# SCH_Konwerter-Hal-Elektrody_2026-02-06.net
KiCad netlist of a schematic drawn in EasyEDA
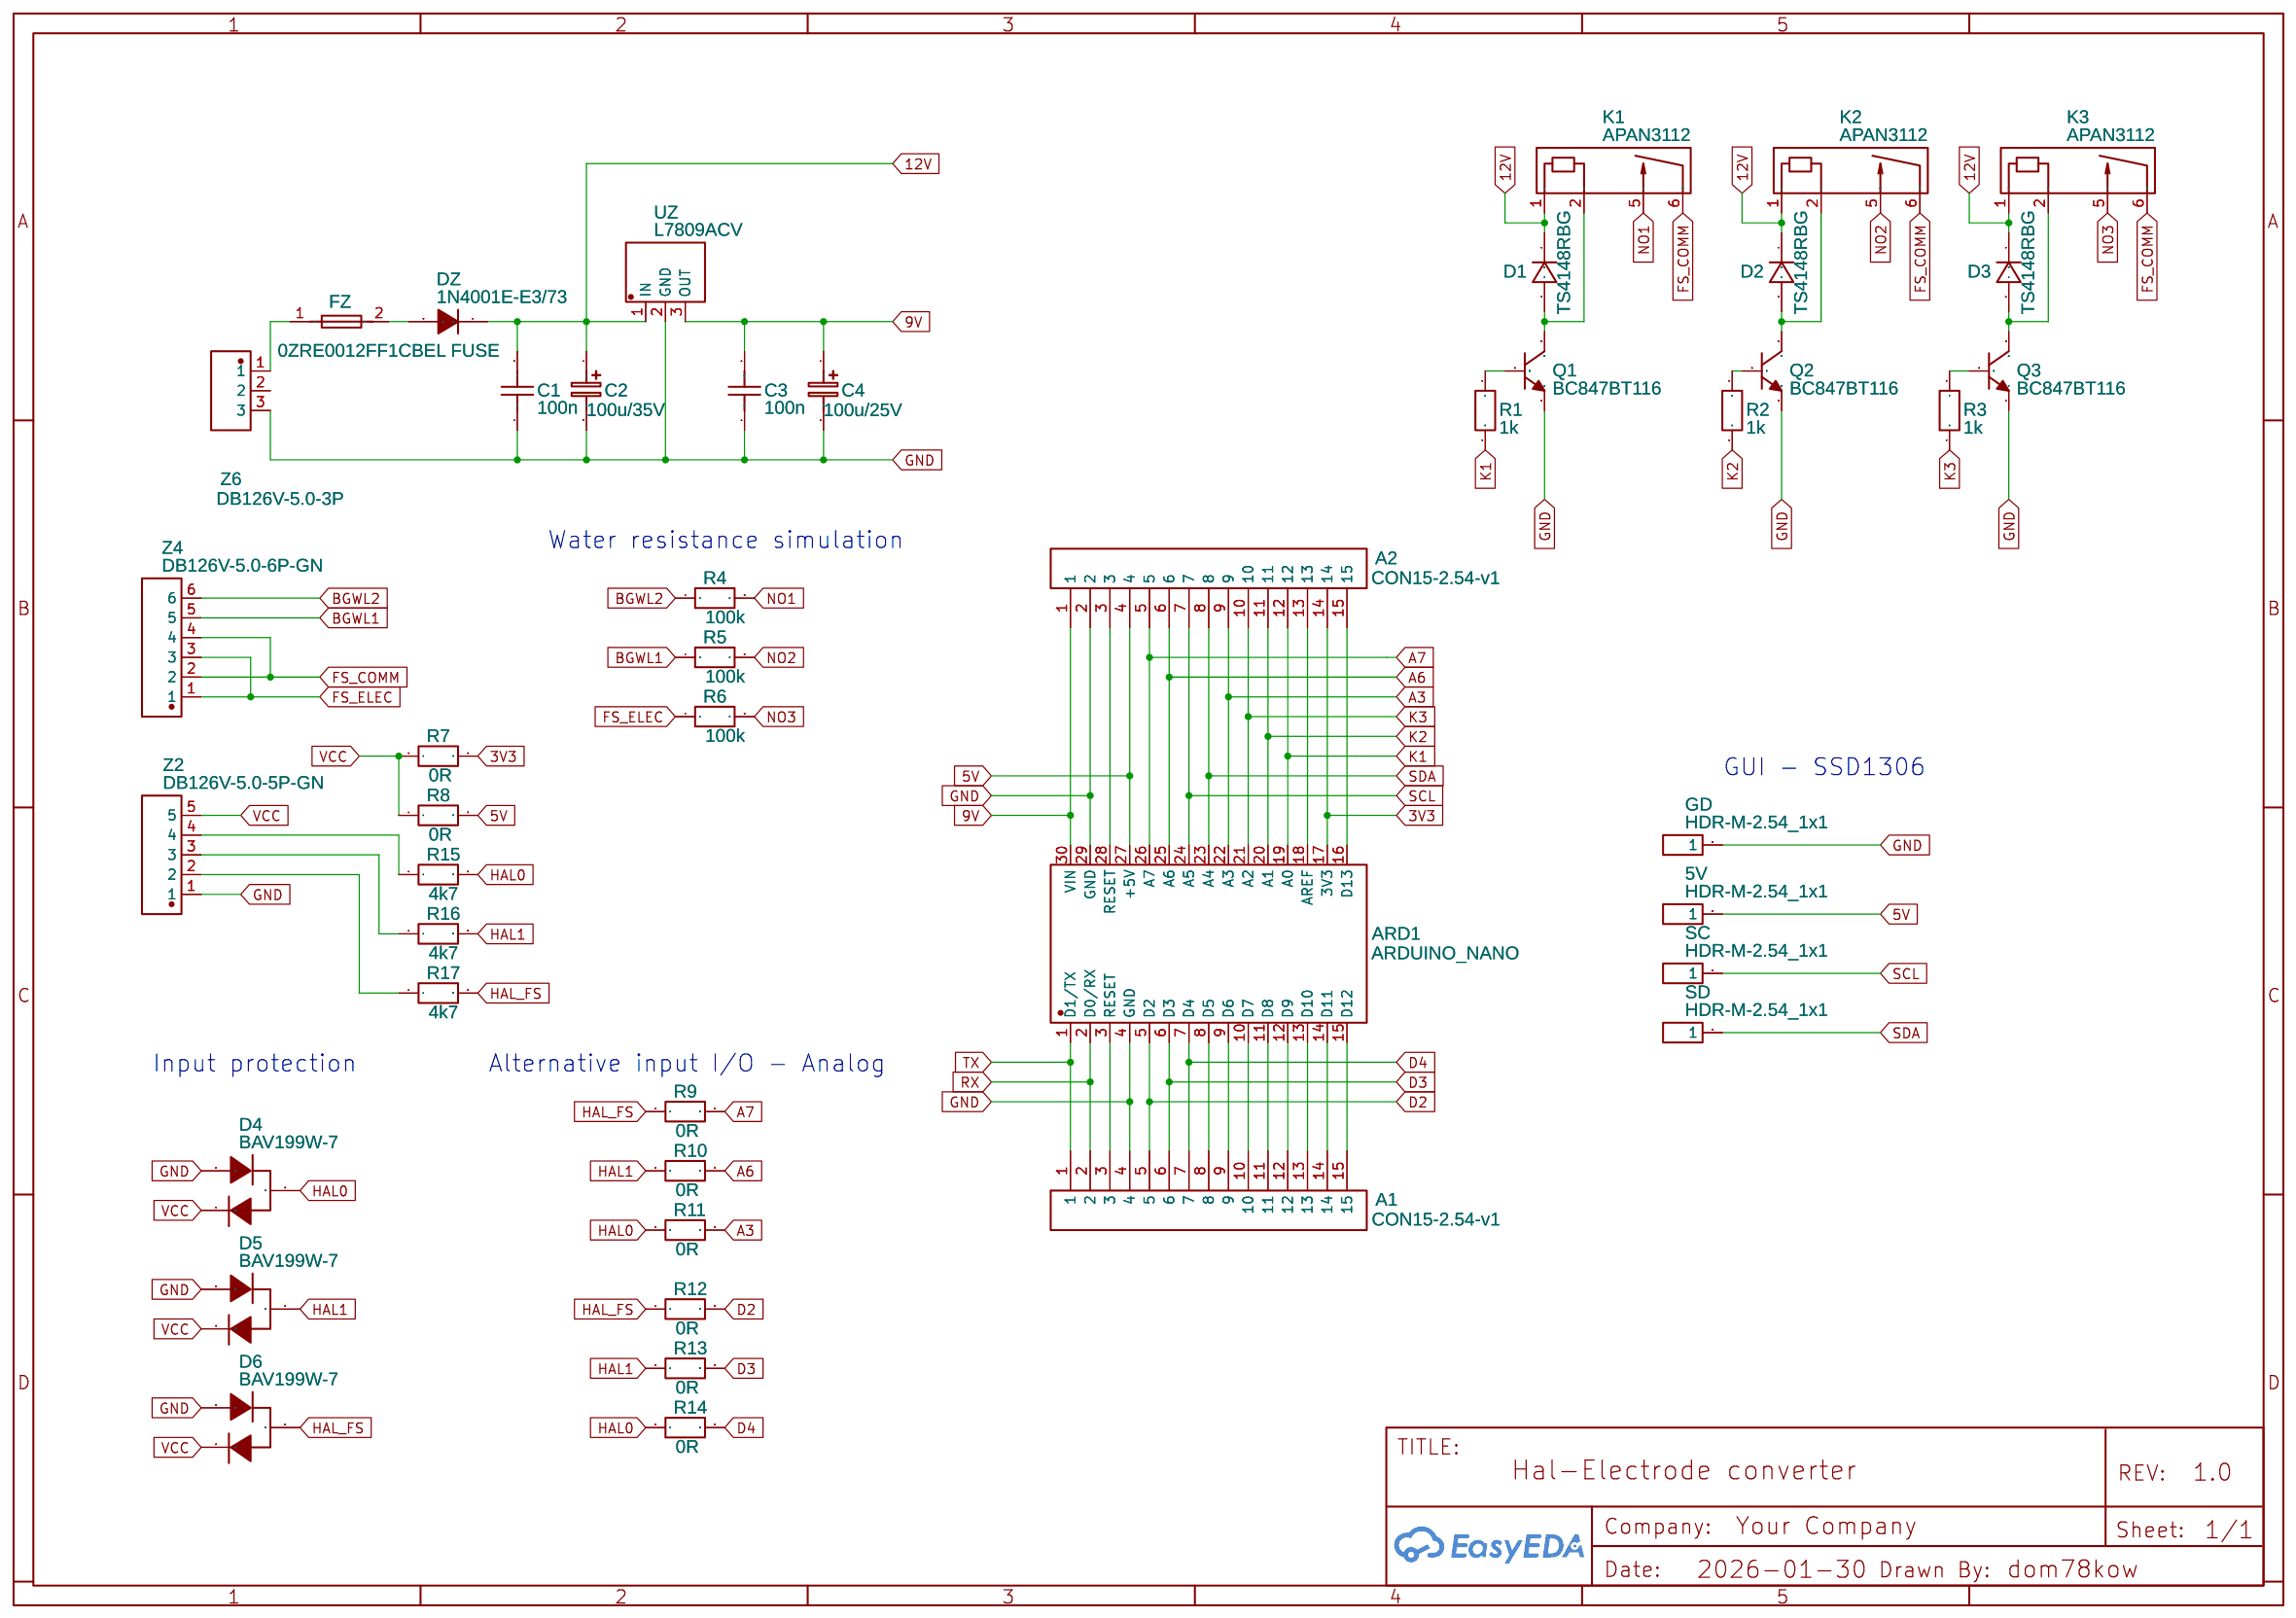
[diagram p0: schematic sheet]

(export (version "E")
  (design (tool "Eeschema 10.0.6"))
  (components
    (comp (ref "5V") (value "HDR-M-2.54_1x1") (libsource (lib "") (part "HDR-M-2.54_1x1_1")))
    (comp (ref "A1") (value "CON15-2.54-v1") (libsource (lib "") (part "CON15-2.54-v1")))
    (comp (ref "A2") (value "CON15-2.54-v1") (libsource (lib "") (part "CON15-2.54-v1_1")))
    (comp (ref "ARD1") (value "ARDUINO_NANO") (libsource (lib "") (part "ARDUINO_NANO")))
    (comp (ref "C1") (value "100n") (libsource (lib "") (part "C_1206_US")))
    (comp (ref "C2") (value "100u/35V") (libsource (lib "") (part "CE_TH_D5.0×F2.0_EU")))
    (comp (ref "C3") (value "100n") (libsource (lib "") (part "C_1206_US")))
    (comp (ref "C4") (value "100u/25V") (libsource (lib "") (part "CE_TH_D5.0×F2.0_EU")))
    (comp (ref "D1")
      (value "TS4148RBG")
      (fields (field (name "Manufacturer Part") "CD4148WP") (field (name "Manufacturer") "SUP(美隆)"))
      (libsource (lib "") (part "CD4148WP_C112371"))
    )
    (comp (ref "D2")
      (value "TS4148RBG")
      (fields (field (name "Manufacturer Part") "CD4148WP") (field (name "Manufacturer") "SUP(美隆)"))
      (libsource (lib "") (part "CD4148WP_C112371"))
    )
    (comp (ref "D3")
      (value "TS4148RBG")
      (fields (field (name "Manufacturer Part") "CD4148WP") (field (name "Manufacturer") "SUP(美隆)"))
      (libsource (lib "") (part "CD4148WP_C112371"))
    )
    (comp (ref "D4")
      (value "BAV199W-7")
      (fields (field (name "Manufacturer") "DIODES(美台)"))
      (libsource (lib "") (part "BAV199W-7"))
    )
    (comp (ref "D5")
      (value "BAV199W-7")
      (fields (field (name "Manufacturer") "DIODES(美台)"))
      (libsource (lib "") (part "BAV199W-7"))
    )
    (comp (ref "D6")
      (value "BAV199W-7")
      (fields (field (name "Manufacturer") "DIODES(美台)"))
      (libsource (lib "") (part "BAV199W-7"))
    )
    (comp (ref "DZ")
      (value "1N4001E-E3/73")
      (fields (field (name "Manufacturer") "VISHAY(威世)"))
      (libsource (lib "") (part "1N4001E-E3/73"))
    )
    (comp (ref "FZ")
      (value "0ZRE0012FF1CBEL FUSE")
      (fields (field (name "Manufacturer Part") "SCT 2.5A") (field (name "Manufacturer") "Skygate(天宇匹克)"))
      (libsource (lib "") (part "SCT 2.5A"))
    )
    (comp (ref "GD") (value "HDR-M-2.54_1x1") (libsource (lib "") (part "HDR-M-2.54_1x1_2")))
    (comp (ref "K1")
      (value "APAN3112")
      (fields (field (name "Manufacturer Part") "APAN3105") (field (name "Manufacturer") "PANASONIC(松下)"))
      (libsource (lib "") (part "APAN3105"))
    )
    (comp (ref "K2")
      (value "APAN3112")
      (fields (field (name "Manufacturer Part") "APAN3105") (field (name "Manufacturer") "PANASONIC(松下)"))
      (libsource (lib "") (part "APAN3105"))
    )
    (comp (ref "K3")
      (value "APAN3112")
      (fields (field (name "Manufacturer Part") "APAN3105") (field (name "Manufacturer") "PANASONIC(松下)"))
      (libsource (lib "") (part "APAN3105"))
    )
    (comp (ref "Q1")
      (value "BC847BT116")
      (fields (field (name "Manufacturer") "ROHM(罗姆)"))
      (libsource (lib "") (part "BC847BT116"))
    )
    (comp (ref "Q2")
      (value "BC847BT116")
      (fields (field (name "Manufacturer") "ROHM(罗姆)"))
      (libsource (lib "") (part "BC847BT116"))
    )
    (comp (ref "Q3")
      (value "BC847BT116")
      (fields (field (name "Manufacturer") "ROHM(罗姆)"))
      (libsource (lib "") (part "BC847BT116"))
    )
    (comp (ref "R1") (value "1k") (libsource (lib "") (part "R_1206_EU_1")))
    (comp (ref "R2") (value "1k") (libsource (lib "") (part "R_1206_EU_1")))
    (comp (ref "R3") (value "1k") (libsource (lib "") (part "R_1206_EU_1")))
    (comp (ref "R4") (value "100k") (libsource (lib "") (part "R_1206_EU")))
    (comp (ref "R5") (value "100k") (libsource (lib "") (part "R_1206_EU")))
    (comp (ref "R6") (value "100k") (libsource (lib "") (part "R_1206_EU")))
    (comp (ref "R7") (value "0R") (libsource (lib "") (part "R_1206_EU")))
    (comp (ref "R8") (value "0R") (libsource (lib "") (part "R_1206_EU")))
    (comp (ref "R9") (value "0R") (libsource (lib "") (part "R_1206_EU")))
    (comp (ref "R10") (value "0R") (libsource (lib "") (part "R_1206_EU")))
    (comp (ref "R11") (value "0R") (libsource (lib "") (part "R_1206_EU")))
    (comp (ref "R12") (value "0R") (libsource (lib "") (part "R_1206_EU")))
    (comp (ref "R13") (value "0R") (libsource (lib "") (part "R_1206_EU")))
    (comp (ref "R14") (value "0R") (libsource (lib "") (part "R_1206_EU")))
    (comp (ref "R15") (value "4k7") (libsource (lib "") (part "R_1206_EU")))
    (comp (ref "R16") (value "4k7") (libsource (lib "") (part "R_1206_EU")))
    (comp (ref "R17") (value "4k7") (libsource (lib "") (part "R_1206_EU")))
    (comp (ref "SC") (value "HDR-M-2.54_1x1") (libsource (lib "") (part "HDR-M-2.54_1x1")))
    (comp (ref "SD") (value "HDR-M-2.54_1x1") (libsource (lib "") (part "HDR-M-2.54_1x1_3")))
    (comp (ref "UZ")
      (value "L7809ACV")
      (fields (field (name "Manufacturer Part") "L7812ACV") (field (name "Manufacturer") "ST(意法半导体)"))
      (libsource (lib "") (part "L7812ACV"))
    )
    (comp (ref "Z2")
      (value "DB126V-5.0-5P-GN")
      (fields
        (field (name "Manufacturer Part") "DB126V-5.0-5P-GN-P")
        (field (name "Manufacturer") "DIBO(地博电气)")
      )
      (libsource (lib "") (part "DB126V-5.0-5P-GN"))
    )
    (comp (ref "Z4")
      (value "DB126V-5.0-6P-GN")
      (fields
        (field (name "Manufacturer Part") "DB126V-5.0-6P-GN-P")
        (field (name "Manufacturer") "DORABO(地博电气)")
      )
      (libsource (lib "") (part "DB126V-5.0-6P-GN"))
    )
    (comp (ref "Z6")
      (value "DB126V-5.0-3P")
      (fields
        (field (name "Manufacturer Part") "DB126V-5.0-3P-GN")
        (field (name "Manufacturer") "DORABO(地博电气)")
      )
      (libsource (lib "") (part "DB126V-5.0-3P"))
    )
  )
  (nets
    (net (code "1") (name "3V3") (class "Default")
      (node (ref "A2") (pin "14") (pinfunction "14_14") (pintype "unspecified"))
      (node (ref "ARD1") (pin "17") (pinfunction "3V3_17") (pintype "unspecified"))
      (node (ref "R7") (pin "2") (pinfunction "2_2") (pintype "unspecified"))
    )
    (net (code "2") (name "5V") (class "Default")
      (node (ref "5V") (pin "1") (pinfunction "1_1") (pintype "input"))
      (node (ref "A2") (pin "4") (pinfunction "4_4") (pintype "unspecified"))
      (node (ref "ARD1") (pin "27") (pinfunction "+5V_27") (pintype "unspecified"))
      (node (ref "R8") (pin "2") (pinfunction "2_2") (pintype "unspecified"))
    )
    (net (code "3") (name "9V") (class "Default")
      (node (ref "A2") (pin "1") (pinfunction "1_1") (pintype "unspecified"))
      (node (ref "ARD1") (pin "30") (pinfunction "VIN_30") (pintype "unspecified"))
      (node (ref "C3") (pin "2") (pinfunction "2_2") (pintype "unspecified"))
      (node (ref "C4") (pin "1") (pinfunction "1_1") (pintype "unspecified"))
      (node (ref "UZ") (pin "3") (pinfunction "OUT_3") (pintype "unspecified"))
    )
    (net (code "4") (name "12V") (class "Default")
      (node (ref "C1") (pin "2") (pinfunction "2_2") (pintype "unspecified"))
      (node (ref "C2") (pin "1") (pinfunction "1_1") (pintype "unspecified"))
      (node (ref "D1") (pin "1") (pinfunction "C_1") (pintype "unspecified"))
      (node (ref "D2") (pin "1") (pinfunction "C_1") (pintype "unspecified"))
      (node (ref "D3") (pin "1") (pinfunction "C_1") (pintype "unspecified"))
      (node (ref "DZ") (pin "1") (pinfunction "K_1") (pintype "unspecified"))
      (node (ref "K1") (pin "1") (pinfunction "1_1") (pintype "unspecified"))
      (node (ref "K2") (pin "1") (pinfunction "1_1") (pintype "unspecified"))
      (node (ref "K3") (pin "1") (pinfunction "1_1") (pintype "unspecified"))
      (node (ref "UZ") (pin "1") (pinfunction "IN_1") (pintype "unspecified"))
    )
    (net (code "5") (name "A3") (class "Default")
      (node (ref "A2") (pin "9") (pinfunction "9_9") (pintype "unspecified"))
      (node (ref "ARD1") (pin "22") (pinfunction "A3_22") (pintype "unspecified"))
      (node (ref "R11") (pin "2") (pinfunction "2_2") (pintype "unspecified"))
    )
    (net (code "6") (name "A6") (class "Default")
      (node (ref "A2") (pin "6") (pinfunction "6_6") (pintype "unspecified"))
      (node (ref "ARD1") (pin "25") (pinfunction "A6_25") (pintype "unspecified"))
      (node (ref "R10") (pin "2") (pinfunction "2_2") (pintype "unspecified"))
    )
    (net (code "7") (name "A7") (class "Default")
      (node (ref "A2") (pin "5") (pinfunction "5_5") (pintype "unspecified"))
      (node (ref "ARD1") (pin "26") (pinfunction "A7_26") (pintype "unspecified"))
      (node (ref "R9") (pin "2") (pinfunction "2_2") (pintype "unspecified"))
    )
    (net (code "8") (name "BGWL1") (class "Default")
      (node (ref "R5") (pin "1") (pinfunction "1_1") (pintype "unspecified"))
      (node (ref "Z4") (pin "5") (pinfunction "5_5") (pintype "unspecified"))
    )
    (net (code "9") (name "BGWL2") (class "Default")
      (node (ref "R4") (pin "1") (pinfunction "1_1") (pintype "unspecified"))
      (node (ref "Z4") (pin "6") (pinfunction "6_6") (pintype "unspecified"))
    )
    (net (code "10") (name "D2") (class "Default")
      (node (ref "A1") (pin "5") (pinfunction "5_5") (pintype "unspecified"))
      (node (ref "ARD1") (pin "5") (pinfunction "D2_5") (pintype "unspecified"))
      (node (ref "R12") (pin "2") (pinfunction "2_2") (pintype "unspecified"))
    )
    (net (code "11") (name "D3") (class "Default")
      (node (ref "A1") (pin "6") (pinfunction "6_6") (pintype "unspecified"))
      (node (ref "ARD1") (pin "6") (pinfunction "D3_6") (pintype "unspecified"))
      (node (ref "R13") (pin "2") (pinfunction "2_2") (pintype "unspecified"))
    )
    (net (code "12") (name "D4") (class "Default")
      (node (ref "A1") (pin "7") (pinfunction "7_7") (pintype "unspecified"))
      (node (ref "ARD1") (pin "7") (pinfunction "D4_7") (pintype "unspecified"))
      (node (ref "R14") (pin "2") (pinfunction "2_2") (pintype "unspecified"))
    )
    (net (code "13") (name "FS_COMM") (class "Default")
      (node (ref "K1") (pin "6") (pinfunction "COM_6") (pintype "unspecified"))
      (node (ref "K2") (pin "6") (pinfunction "COM_6") (pintype "unspecified"))
      (node (ref "K3") (pin "6") (pinfunction "COM_6") (pintype "unspecified"))
      (node (ref "Z4") (pin "2") (pinfunction "2_2") (pintype "unspecified"))
      (node (ref "Z4") (pin "4") (pinfunction "4_4") (pintype "unspecified"))
    )
    (net (code "14") (name "FS_ELEC") (class "Default")
      (node (ref "R6") (pin "1") (pinfunction "1_1") (pintype "unspecified"))
      (node (ref "Z4") (pin "1") (pinfunction "1_1") (pintype "unspecified"))
      (node (ref "Z4") (pin "3") (pinfunction "3_3") (pintype "unspecified"))
    )
    (net (code "15") (name "GND") (class "Default")
      (node (ref "A1") (pin "4") (pinfunction "4_4") (pintype "unspecified"))
      (node (ref "A2") (pin "2") (pinfunction "2_2") (pintype "unspecified"))
      (node (ref "ARD1") (pin "29") (pinfunction "GND_29") (pintype "unspecified"))
      (node (ref "ARD1") (pin "4") (pinfunction "GND_4") (pintype "unspecified"))
      (node (ref "C1") (pin "1") (pinfunction "1_1") (pintype "unspecified"))
      (node (ref "C2") (pin "2") (pinfunction "2_2") (pintype "unspecified"))
      (node (ref "C3") (pin "1") (pinfunction "1_1") (pintype "unspecified"))
      (node (ref "C4") (pin "2") (pinfunction "2_2") (pintype "unspecified"))
      (node (ref "D4") (pin "1") (pinfunction "1_1") (pintype "unspecified"))
      (node (ref "D5") (pin "1") (pinfunction "1_1") (pintype "unspecified"))
      (node (ref "D6") (pin "1") (pinfunction "1_1") (pintype "unspecified"))
      (node (ref "GD") (pin "1") (pinfunction "1_1") (pintype "input"))
      (node (ref "Q1") (pin "1") (pinfunction "E_1") (pintype "input"))
      (node (ref "Q2") (pin "1") (pinfunction "E_1") (pintype "input"))
      (node (ref "Q3") (pin "1") (pinfunction "E_1") (pintype "input"))
      (node (ref "UZ") (pin "2") (pinfunction "GND_2") (pintype "unspecified"))
      (node (ref "Z2") (pin "1") (pinfunction "1_1") (pintype "unspecified"))
      (node (ref "Z6") (pin "3") (pinfunction "3_3") (pintype "unspecified"))
    )
    (net (code "16") (name "HAL0") (class "Default")
      (node (ref "D4") (pin "3") (pinfunction "3_3") (pintype "unspecified"))
      (node (ref "R11") (pin "1") (pinfunction "1_1") (pintype "unspecified"))
      (node (ref "R14") (pin "1") (pinfunction "1_1") (pintype "unspecified"))
      (node (ref "R15") (pin "2") (pinfunction "2_2") (pintype "unspecified"))
    )
    (net (code "17") (name "HAL1") (class "Default")
      (node (ref "D5") (pin "3") (pinfunction "3_3") (pintype "unspecified"))
      (node (ref "R10") (pin "1") (pinfunction "1_1") (pintype "unspecified"))
      (node (ref "R13") (pin "1") (pinfunction "1_1") (pintype "unspecified"))
      (node (ref "R16") (pin "2") (pinfunction "2_2") (pintype "unspecified"))
    )
    (net (code "18") (name "HAL_FS") (class "Default")
      (node (ref "D6") (pin "3") (pinfunction "3_3") (pintype "unspecified"))
      (node (ref "R12") (pin "1") (pinfunction "1_1") (pintype "unspecified"))
      (node (ref "R17") (pin "2") (pinfunction "2_2") (pintype "unspecified"))
      (node (ref "R9") (pin "1") (pinfunction "1_1") (pintype "unspecified"))
    )
    (net (code "19") (name "K1") (class "Default")
      (node (ref "A2") (pin "12") (pinfunction "12_12") (pintype "unspecified"))
      (node (ref "ARD1") (pin "19") (pinfunction "A0_19") (pintype "unspecified"))
      (node (ref "R1") (pin "2") (pinfunction "2_2") (pintype "unspecified"))
    )
    (net (code "20") (name "K2") (class "Default")
      (node (ref "A2") (pin "11") (pinfunction "11_11") (pintype "unspecified"))
      (node (ref "ARD1") (pin "20") (pinfunction "A1_20") (pintype "unspecified"))
      (node (ref "R2") (pin "2") (pinfunction "2_2") (pintype "unspecified"))
    )
    (net (code "21") (name "K3") (class "Default")
      (node (ref "A2") (pin "10") (pinfunction "10_10") (pintype "unspecified"))
      (node (ref "ARD1") (pin "21") (pinfunction "A2_21") (pintype "unspecified"))
      (node (ref "R3") (pin "2") (pinfunction "2_2") (pintype "unspecified"))
    )
    (net (code "22") (name "NO1") (class "Default")
      (node (ref "K1") (pin "5") (pinfunction "ON_5") (pintype "unspecified"))
      (node (ref "R4") (pin "2") (pinfunction "2_2") (pintype "unspecified"))
    )
    (net (code "23") (name "NO2") (class "Default")
      (node (ref "K2") (pin "5") (pinfunction "ON_5") (pintype "unspecified"))
      (node (ref "R5") (pin "2") (pinfunction "2_2") (pintype "unspecified"))
    )
    (net (code "24") (name "NO3") (class "Default")
      (node (ref "K3") (pin "5") (pinfunction "ON_5") (pintype "unspecified"))
      (node (ref "R6") (pin "2") (pinfunction "2_2") (pintype "unspecified"))
    )
    (net (code "25") (name "Net-(A1-Pad3)") (class "Default")
      (node (ref "A1") (pin "3") (pinfunction "3_3") (pintype "unspecified"))
      (node (ref "ARD1") (pin "3") (pinfunction "RESET_3") (pintype "unspecified"))
    )
    (net (code "26") (name "Net-(A2-Pad3)") (class "Default")
      (node (ref "A2") (pin "3") (pinfunction "3_3") (pintype "unspecified"))
      (node (ref "ARD1") (pin "28") (pinfunction "RESET_28") (pintype "unspecified"))
    )
    (net (code "27") (name "Net-(ARD1-AREF)") (class "Default")
      (node (ref "A2") (pin "13") (pinfunction "13_13") (pintype "unspecified"))
      (node (ref "ARD1") (pin "18") (pinfunction "AREF_18") (pintype "unspecified"))
    )
    (net (code "28") (name "Net-(ARD1-D5)") (class "Default")
      (node (ref "A1") (pin "8") (pinfunction "8_8") (pintype "unspecified"))
      (node (ref "ARD1") (pin "8") (pinfunction "D5_8") (pintype "unspecified"))
    )
    (net (code "29") (name "Net-(ARD1-D6)") (class "Default")
      (node (ref "A1") (pin "9") (pinfunction "9_9") (pintype "unspecified"))
      (node (ref "ARD1") (pin "9") (pinfunction "D6_9") (pintype "unspecified"))
    )
    (net (code "30") (name "Net-(ARD1-D7)") (class "Default")
      (node (ref "A1") (pin "10") (pinfunction "10_10") (pintype "unspecified"))
      (node (ref "ARD1") (pin "10") (pinfunction "D7_10") (pintype "unspecified"))
    )
    (net (code "31") (name "Net-(ARD1-D8)") (class "Default")
      (node (ref "A1") (pin "11") (pinfunction "11_11") (pintype "unspecified"))
      (node (ref "ARD1") (pin "11") (pinfunction "D8_11") (pintype "unspecified"))
    )
    (net (code "32") (name "Net-(ARD1-D9)") (class "Default")
      (node (ref "A1") (pin "12") (pinfunction "12_12") (pintype "unspecified"))
      (node (ref "ARD1") (pin "12") (pinfunction "D9_12") (pintype "unspecified"))
    )
    (net (code "33") (name "Net-(ARD1-D10)") (class "Default")
      (node (ref "A1") (pin "13") (pinfunction "13_13") (pintype "unspecified"))
      (node (ref "ARD1") (pin "13") (pinfunction "D10_13") (pintype "unspecified"))
    )
    (net (code "34") (name "Net-(ARD1-D11)") (class "Default")
      (node (ref "A1") (pin "14") (pinfunction "14_14") (pintype "unspecified"))
      (node (ref "ARD1") (pin "14") (pinfunction "D11_14") (pintype "unspecified"))
    )
    (net (code "35") (name "Net-(ARD1-D12)") (class "Default")
      (node (ref "A1") (pin "15") (pinfunction "15_15") (pintype "unspecified"))
      (node (ref "ARD1") (pin "15") (pinfunction "D12_15") (pintype "unspecified"))
    )
    (net (code "36") (name "Net-(ARD1-D13)") (class "Default")
      (node (ref "A2") (pin "15") (pinfunction "15_15") (pintype "unspecified"))
      (node (ref "ARD1") (pin "16") (pinfunction "D13_16") (pintype "unspecified"))
    )
    (net (code "37") (name "Net-(D1-A)") (class "Default")
      (node (ref "D1") (pin "2") (pinfunction "A_2") (pintype "unspecified"))
      (node (ref "K1") (pin "2") (pinfunction "2_2") (pintype "unspecified"))
      (node (ref "Q1") (pin "3") (pinfunction "C_3") (pintype "input"))
    )
    (net (code "38") (name "Net-(D2-A)") (class "Default")
      (node (ref "D2") (pin "2") (pinfunction "A_2") (pintype "unspecified"))
      (node (ref "K2") (pin "2") (pinfunction "2_2") (pintype "unspecified"))
      (node (ref "Q2") (pin "3") (pinfunction "C_3") (pintype "input"))
    )
    (net (code "39") (name "Net-(D3-A)") (class "Default")
      (node (ref "D3") (pin "2") (pinfunction "A_2") (pintype "unspecified"))
      (node (ref "K3") (pin "2") (pinfunction "2_2") (pintype "unspecified"))
      (node (ref "Q3") (pin "3") (pinfunction "C_3") (pintype "input"))
    )
    (net (code "40") (name "Net-(DZ-A)") (class "Default")
      (node (ref "DZ") (pin "2") (pinfunction "A_2") (pintype "unspecified"))
      (node (ref "FZ") (pin "2") (pinfunction "2_2") (pintype "unspecified"))
    )
    (net (code "41") (name "Net-(FZ-Pad1)") (class "Default")
      (node (ref "FZ") (pin "1") (pinfunction "1_1") (pintype "unspecified"))
      (node (ref "Z6") (pin "1") (pinfunction "1_1") (pintype "unspecified"))
    )
    (net (code "42") (name "Net-(Q1-B)") (class "Default")
      (node (ref "Q1") (pin "2") (pinfunction "B_2") (pintype "input"))
      (node (ref "R1") (pin "1") (pinfunction "1_1") (pintype "unspecified"))
    )
    (net (code "43") (name "Net-(Q2-B)") (class "Default")
      (node (ref "Q2") (pin "2") (pinfunction "B_2") (pintype "input"))
      (node (ref "R2") (pin "1") (pinfunction "1_1") (pintype "unspecified"))
    )
    (net (code "44") (name "Net-(Q3-B)") (class "Default")
      (node (ref "Q3") (pin "2") (pinfunction "B_2") (pintype "input"))
      (node (ref "R3") (pin "1") (pinfunction "1_1") (pintype "unspecified"))
    )
    (net (code "45") (name "Net-(R15-Pad1)") (class "Default")
      (node (ref "R15") (pin "1") (pinfunction "1_1") (pintype "unspecified"))
      (node (ref "Z2") (pin "4") (pinfunction "4_4") (pintype "unspecified"))
    )
    (net (code "46") (name "Net-(R16-Pad1)") (class "Default")
      (node (ref "R16") (pin "1") (pinfunction "1_1") (pintype "unspecified"))
      (node (ref "Z2") (pin "3") (pinfunction "3_3") (pintype "unspecified"))
    )
    (net (code "47") (name "Net-(R17-Pad1)") (class "Default")
      (node (ref "R17") (pin "1") (pinfunction "1_1") (pintype "unspecified"))
      (node (ref "Z2") (pin "2") (pinfunction "2_2") (pintype "unspecified"))
    )
    (net (code "48") (name "RX") (class "Default")
      (node (ref "A1") (pin "2") (pinfunction "2_2") (pintype "unspecified"))
      (node (ref "ARD1") (pin "2") (pinfunction "D0/RX_2") (pintype "unspecified"))
    )
    (net (code "49") (name "SCL") (class "Default")
      (node (ref "A2") (pin "7") (pinfunction "7_7") (pintype "unspecified"))
      (node (ref "ARD1") (pin "24") (pinfunction "A5_24") (pintype "unspecified"))
      (node (ref "SC") (pin "1") (pinfunction "1_1") (pintype "input"))
    )
    (net (code "50") (name "SDA") (class "Default")
      (node (ref "A2") (pin "8") (pinfunction "8_8") (pintype "unspecified"))
      (node (ref "ARD1") (pin "23") (pinfunction "A4_23") (pintype "unspecified"))
      (node (ref "SD") (pin "1") (pinfunction "1_1") (pintype "input"))
    )
    (net (code "51") (name "TX") (class "Default")
      (node (ref "A1") (pin "1") (pinfunction "1_1") (pintype "unspecified"))
      (node (ref "ARD1") (pin "1") (pinfunction "D1/TX_1") (pintype "unspecified"))
    )
    (net (code "52") (name "VCC") (class "Default")
      (node (ref "D4") (pin "2") (pinfunction "2_2") (pintype "unspecified"))
      (node (ref "D5") (pin "2") (pinfunction "2_2") (pintype "unspecified"))
      (node (ref "D6") (pin "2") (pinfunction "2_2") (pintype "unspecified"))
      (node (ref "R7") (pin "1") (pinfunction "1_1") (pintype "unspecified"))
      (node (ref "R8") (pin "1") (pinfunction "1_1") (pintype "unspecified"))
      (node (ref "Z2") (pin "5") (pinfunction "5_5") (pintype "unspecified"))
    )
    (net (code "53") (name "unconnected-(Z6-Pad2)") (class "Default")
      (node (ref "Z6") (pin "2") (pinfunction "2_2") (pintype "unspecified"))
    )
  )
)
